# power1.net
KiCad netlist of a schematic drawn in Altium Designer
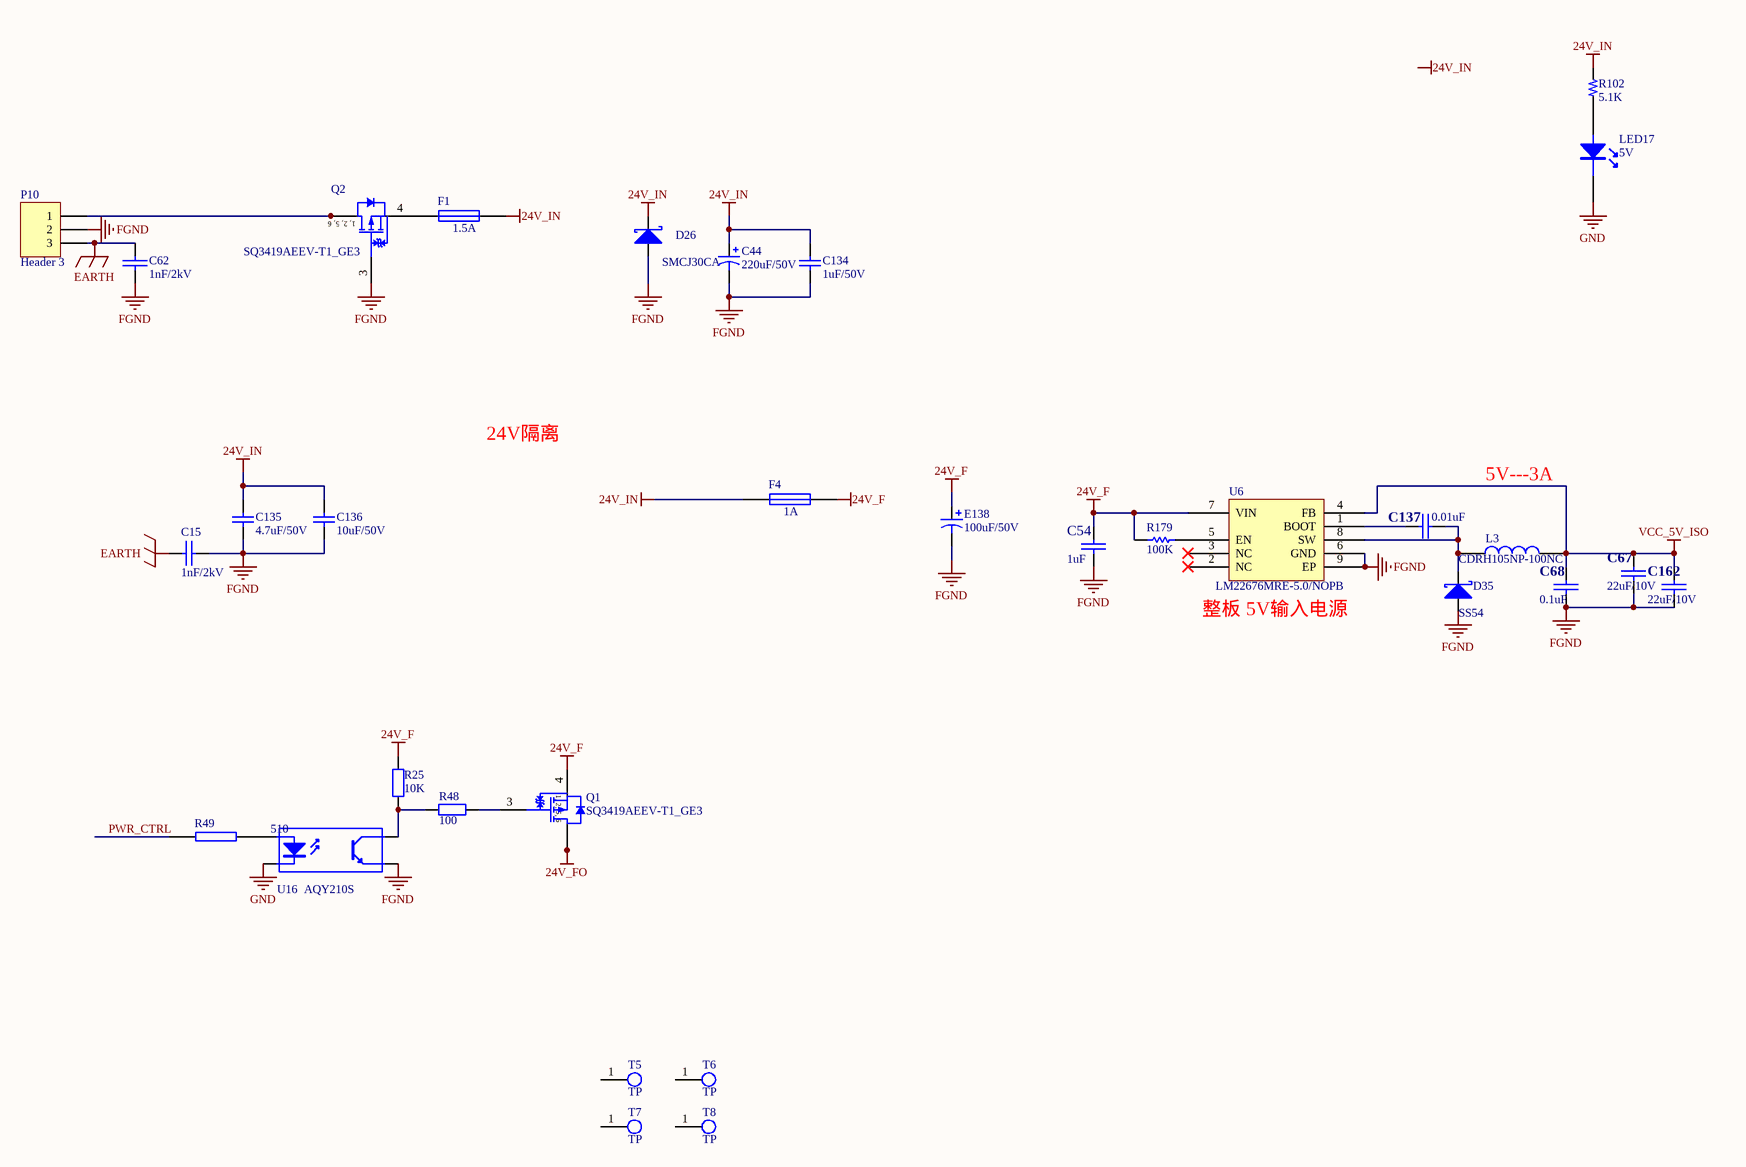
[diagram p0: power1.SchDoc]

(export (version "E")
  (design (tool "Eeschema 10.0.6"))
  (components
    (comp (ref "C15")
      (value "1nF/2kV")
      (footprint "1206C")
      (description "Capacitor")
      (libsource (lib "*") (part "CAP"))
    )
    (comp (ref "C44")
      (value "220uF/50V")
      (footprint "Φ10×10")
      (description "Polarized Capacitor (Radial)")
      (fields (field (name "PUBLISHER") "Altium Limited"))
      (libsource (lib "Miscellaneous Devices") (part "Cap Pol1"))
    )
    (comp (ref "C54")
      (value "1uF")
      (footprint "0603C")
      (description "Capacitor")
      (libsource (lib "*") (part "CAP"))
    )
    (comp (ref "C62")
      (value "1nF/2kV")
      (footprint "1206C")
      (description "Capacitor")
      (libsource (lib "*") (part "CAP"))
    )
    (comp (ref "C67")
      (value "22uF/10V")
      (footprint "1210C")
      (description "Capacitor")
      (libsource (lib "*") (part "CAP"))
    )
    (comp (ref "C68")
      (value "0.1uF")
      (footprint "0603C")
      (description "Capacitor")
      (libsource (lib "*") (part "CAP"))
    )
    (comp (ref "C134")
      (value "1uF/50V")
      (footprint "1210C")
      (description "Capacitor")
      (fields (field (name "PUBLISHER") "Altium Limited"))
      (libsource (lib "Miscellaneous Devices") (part "Cap"))
    )
    (comp (ref "C135")
      (value "4.7uF/50V")
      (footprint "1210C")
      (description "Capacitor")
      (fields (field (name "PUBLISHER") "Altium Limited"))
      (libsource (lib "Miscellaneous Devices") (part "Cap"))
    )
    (comp (ref "C136")
      (value "10uF/50V")
      (footprint "1210C")
      (description "Capacitor")
      (fields (field (name "PUBLISHER") "Altium Limited"))
      (libsource (lib "Miscellaneous Devices") (part "Cap"))
    )
    (comp (ref "C137")
      (value "0.01uF")
      (footprint "0603C")
      (description "Capacitor")
      (libsource (lib "*") (part "CAP"))
    )
    (comp (ref "C162")
      (value "22uF/10V")
      (footprint "1210C")
      (description "Capacitor")
      (libsource (lib "*") (part "CAP"))
    )
    (comp (ref "D26")
      (value "SMCJ30CA")
      (footprint "SMC")
      (description "Schottky Diode")
      (libsource (lib "*") (part "DIODE S"))
    )
    (comp (ref "D35")
      (value "SS54")
      (footprint "SMC")
      (description "Schottky Diode")
      (libsource (lib "*") (part "DIODE S"))
    )
    (comp (ref "E138")
      (value "100uF/50V")
      (footprint "Φ10×10")
      (description "Polarized Capacitor (Radial)")
      (fields (field (name "PUBLISHER") "Altium Limited"))
      (libsource (lib "Miscellaneous Devices") (part "Cap Pol1"))
    )
    (comp (ref "F1")
      (value "1.5A")
      (footprint "1812-F")
      (description "Fuse")
      (fields (field (name "PUBLISHER") "Altium Limited"))
      (libsource (lib "Miscellaneous Devices") (part "Fuse 1"))
    )
    (comp (ref "F4")
      (value "1A")
      (footprint "1812-F")
      (description "Fuse")
      (fields (field (name "PUBLISHER") "Altium Limited"))
      (libsource (lib "Miscellaneous Devices") (part "Fuse 1"))
    )
    (comp (ref "L3") (value "CDRH105NP-100NC") (footprint "CDRH105") (libsource (lib "*") (part "INDUCTOR")))
    (comp (ref "LED17") (value "5V") (footprint "0603LED") (libsource (lib "*") (part "LED")))
    (comp (ref "P10")
      (value "Header 3")
      (footprint "2ETYR-5.08-03P-14-100")
      (description "Header, 3-Pin")
      (fields (field (name "PUBLISHER") "Altium Limited"))
      (libsource (lib "Miscellaneous Connectors") (part "Header 3"))
    )
    (comp (ref "Q1")
      (value "SQ3419AEEV-T1_GE3")
      (footprint "VISH-TSOP-6_V")
      (description "Automotive P-Channel MOSFET, 6.9 A, 40 V, -55 to 175 degC, 6-Pin TSOP, RoHS, Tape and Reel")
      (fields (field (name "MANUFACTURER") "International Rectifier"))
      (libsource (lib "Bogen") (part "SQ3419AEEV-T1_GE3"))
    )
    (comp (ref "Q2")
      (value "SQ3419AEEV-T1_GE3")
      (footprint "VISH-TSOP-6_V")
      (description "Automotive P-Channel MOSFET, 6.9 A, 40 V, -55 to 175 degC, 6-Pin TSOP, RoHS, Tape and Reel")
      (fields (field (name "MANUFACTURER") "International Rectifier"))
      (libsource (lib "Bogen") (part "SQ3419AEEV-T1_GE3"))
    )
    (comp (ref "R25") (value "10K") (footprint "0603R") (libsource (lib "MQlibrary") (part "Res0805M")))
    (comp (ref "R48") (value "100") (footprint "0603R") (libsource (lib "") (part "Res0805M_1")))
    (comp (ref "R49") (value "510") (footprint "0603R") (libsource (lib "*") (part "RES2")))
    (comp (ref "R102")
      (value "5.1K")
      (footprint "0603R")
      (description "R")
      (libsource (lib "JRJ_1") (part "R"))
    )
    (comp (ref "R179")
      (value "100K")
      (footprint "0603R")
      (description "Resistor")
      (fields (field (name "PUBLISHER") "Altium Limited"))
      (libsource (lib "Miscellaneous Devices") (part "Res1"))
    )
    (comp (ref "T5") (value "TP") (footprint "m2.5") (libsource (lib "Schlib_20110825") (part "TP")))
    (comp (ref "T6") (value "TP") (footprint "m2.5") (libsource (lib "Schlib_20110825") (part "TP")))
    (comp (ref "T7") (value "TP") (footprint "m2.5") (libsource (lib "Schlib_20110825") (part "TP")))
    (comp (ref "T8") (value "TP") (footprint "m2.5") (libsource (lib "Schlib_20110825") (part "TP")))
    (comp (ref "U6")
      (value "LM22676MRE-5.0/NOPB")
      (footprint "SOP127P600X168_HS-8N")
      (libsource (lib "Schlib1") (part "LM22676MR-5.0"))
    )
    (comp (ref "U16")
      (value "AQY210S")
      (footprint "sop4")
      (description "4-Pin Phototransistor Optocoupler")
      (fields (field (name "PUBLISHER") "Altium Limited"))
      (libsource (lib "Miscellaneous Devices") (part "Optoisolator1"))
    )
  )
  (nets
    (net (code "1") (name "/PWR_CTRL") (class "Default")
      (node (ref "R49") (pin "2") (pinfunction "2_2") (pintype "passive"))
    )
    (net (code "2") (name "24V_F") (class "Default")
      (node (ref "C54") (pin "2") (pinfunction "2_2") (pintype "passive"))
      (node (ref "E138") (pin "1") (pinfunction "1_1") (pintype "passive"))
      (node (ref "F4") (pin "2") (pinfunction "2_2") (pintype "passive"))
      (node (ref "Q1") (pin "4") (pinfunction "S_4") (pintype "passive"))
      (node (ref "R179") (pin "2") (pinfunction "2_2") (pintype "passive"))
      (node (ref "R25") (pin "2") (pinfunction "2_2") (pintype "passive"))
      (node (ref "U6") (pin "7") (pinfunction "VIN_7") (pintype "passive"))
    )
    (net (code "3") (name "24V_FO") (class "Default")
      (node (ref "Q1") (pin "1") (pinfunction "D_1") (pintype "passive"))
      (node (ref "Q1") (pin "2") (pinfunction "D_2") (pintype "passive"))
      (node (ref "Q1") (pin "5") (pinfunction "D_5") (pintype "passive"))
      (node (ref "Q1") (pin "6") (pinfunction "D_6") (pintype "passive"))
    )
    (net (code "4") (name "24V_IN") (class "Default")
      (node (ref "C134") (pin "2") (pinfunction "2_2") (pintype "passive"))
      (node (ref "C135") (pin "2") (pinfunction "2_2") (pintype "passive"))
      (node (ref "C136") (pin "2") (pinfunction "2_2") (pintype "passive"))
      (node (ref "C44") (pin "1") (pinfunction "1_1") (pintype "passive"))
      (node (ref "D26") (pin "2") (pinfunction "K_2") (pintype "passive"))
      (node (ref "F1") (pin "2") (pinfunction "2_2") (pintype "passive"))
      (node (ref "F4") (pin "1") (pinfunction "1_1") (pintype "passive"))
      (node (ref "R102") (pin "2") (pintype "passive"))
    )
    (net (code "5") (name "EARTH") (class "Default")
      (node (ref "C15") (pin "2") (pinfunction "2_2") (pintype "passive"))
      (node (ref "C62") (pin "2") (pinfunction "2_2") (pintype "passive"))
      (node (ref "P10") (pin "3") (pinfunction "3_3") (pintype "passive"))
    )
    (net (code "6") (name "FGND") (class "Default")
      (node (ref "C134") (pin "1") (pinfunction "1_1") (pintype "passive"))
      (node (ref "C135") (pin "1") (pinfunction "1_1") (pintype "passive"))
      (node (ref "C136") (pin "1") (pinfunction "1_1") (pintype "passive"))
      (node (ref "C15") (pin "1") (pinfunction "1_1") (pintype "passive"))
      (node (ref "C162") (pin "2") (pinfunction "2_2") (pintype "passive"))
      (node (ref "C44") (pin "2") (pinfunction "2_2") (pintype "passive"))
      (node (ref "C54") (pin "1") (pinfunction "1_1") (pintype "passive"))
      (node (ref "C62") (pin "1") (pinfunction "1_1") (pintype "passive"))
      (node (ref "C67") (pin "2") (pinfunction "2_2") (pintype "passive"))
      (node (ref "C68") (pin "2") (pinfunction "2_2") (pintype "passive"))
      (node (ref "D26") (pin "1") (pinfunction "A_1") (pintype "passive"))
      (node (ref "D35") (pin "1") (pinfunction "A_1") (pintype "passive"))
      (node (ref "E138") (pin "2") (pinfunction "2_2") (pintype "passive"))
      (node (ref "P10") (pin "2") (pinfunction "2_2") (pintype "passive"))
      (node (ref "Q2") (pin "3") (pinfunction "G_3") (pintype "passive"))
      (node (ref "U16") (pin "3") (pinfunction "E_3") (pintype "passive"))
      (node (ref "U6") (pin "6") (pinfunction "GND_6") (pintype "passive"))
      (node (ref "U6") (pin "9") (pinfunction "EP_9") (pintype "passive"))
    )
    (net (code "7") (name "GND") (class "Default")
      (node (ref "LED17") (pin "2") (pinfunction "2_2") (pintype "passive"))
      (node (ref "U16") (pin "2") (pinfunction "K_2") (pintype "passive"))
    )
    (net (code "8") (name "Net-(D35-K)") (class "Default")
      (node (ref "C137") (pin "1") (pinfunction "1_1") (pintype "passive"))
      (node (ref "D35") (pin "2") (pinfunction "K_2") (pintype "passive"))
      (node (ref "L3") (pin "1") (pinfunction "1_1") (pintype "passive"))
      (node (ref "U6") (pin "8") (pinfunction "SW_8") (pintype "passive"))
    )
    (net (code "9") (name "Net-(LED17-Pad1)") (class "Default")
      (node (ref "LED17") (pin "1") (pinfunction "1_1") (pintype "passive"))
      (node (ref "R102") (pin "1") (pintype "passive"))
    )
    (net (code "10") (name "Net-(P10-Pad1)") (class "Default")
      (node (ref "P10") (pin "1") (pinfunction "1_1") (pintype "passive"))
      (node (ref "Q2") (pin "1") (pinfunction "D_1") (pintype "passive"))
      (node (ref "Q2") (pin "2") (pinfunction "D_2") (pintype "passive"))
      (node (ref "Q2") (pin "5") (pinfunction "D_5") (pintype "passive"))
      (node (ref "Q2") (pin "6") (pinfunction "D_6") (pintype "passive"))
    )
    (net (code "11") (name "Net-(Q1-G)") (class "Default")
      (node (ref "Q1") (pin "3") (pinfunction "G_3") (pintype "passive"))
      (node (ref "R48") (pin "1") (pinfunction "1_1") (pintype "passive"))
    )
    (net (code "12") (name "Net-(Q2-S)") (class "Default")
      (node (ref "F1") (pin "1") (pinfunction "1_1") (pintype "passive"))
      (node (ref "Q2") (pin "4") (pinfunction "S_4") (pintype "passive"))
    )
    (net (code "13") (name "Net-(U6-BOOT)") (class "Default")
      (node (ref "C137") (pin "2") (pinfunction "2_2") (pintype "passive"))
      (node (ref "U6") (pin "1") (pinfunction "BOOT_1") (pintype "passive"))
    )
    (net (code "14") (name "Net-(U6-EN)") (class "Default")
      (node (ref "R179") (pin "1") (pinfunction "1_1") (pintype "passive"))
      (node (ref "U6") (pin "5") (pinfunction "EN_5") (pintype "passive"))
    )
    (net (code "15") (name "Net-(U16-A)") (class "Default")
      (node (ref "R49") (pin "1") (pinfunction "1_1") (pintype "passive"))
      (node (ref "U16") (pin "1") (pinfunction "A_1") (pintype "passive"))
    )
    (net (code "16") (name "Net-(U16-C)") (class "Default")
      (node (ref "R25") (pin "1") (pinfunction "1_1") (pintype "passive"))
      (node (ref "R48") (pin "2") (pinfunction "2_2") (pintype "passive"))
      (node (ref "U16") (pin "4") (pinfunction "C_4") (pintype "passive"))
    )
    (net (code "17") (name "VCC_5V_ISO") (class "Default")
      (node (ref "C162") (pin "1") (pinfunction "1_1") (pintype "passive"))
      (node (ref "C67") (pin "1") (pinfunction "1_1") (pintype "passive"))
      (node (ref "C68") (pin "1") (pinfunction "1_1") (pintype "passive"))
      (node (ref "L3") (pin "2") (pinfunction "2_2") (pintype "passive"))
      (node (ref "U6") (pin "4") (pinfunction "FB_4") (pintype "passive"))
    )
    (net (code "18") (name "unconnected-(T5-Pad1)") (class "Default")
      (node (ref "T5") (pin "1") (pintype "passive"))
    )
    (net (code "19") (name "unconnected-(T6-Pad1)") (class "Default")
      (node (ref "T6") (pin "1") (pintype "passive"))
    )
    (net (code "20") (name "unconnected-(T7-Pad1)") (class "Default")
      (node (ref "T7") (pin "1") (pintype "passive"))
    )
    (net (code "21") (name "unconnected-(T8-Pad1)") (class "Default")
      (node (ref "T8") (pin "1") (pintype "passive"))
    )
    (net (code "22") (name "unconnected-(U6-NC-Pad2)") (class "Default")
      (node (ref "U6") (pin "2") (pinfunction "NC_2") (pintype "passive+no_connect"))
    )
    (net (code "23") (name "unconnected-(U6-NC-Pad3)") (class "Default")
      (node (ref "U6") (pin "3") (pinfunction "NC_3") (pintype "passive+no_connect"))
    )
  )
)
